# High_Side_Drivers.net
KiCad netlist of a schematic drawn in Altium Designer
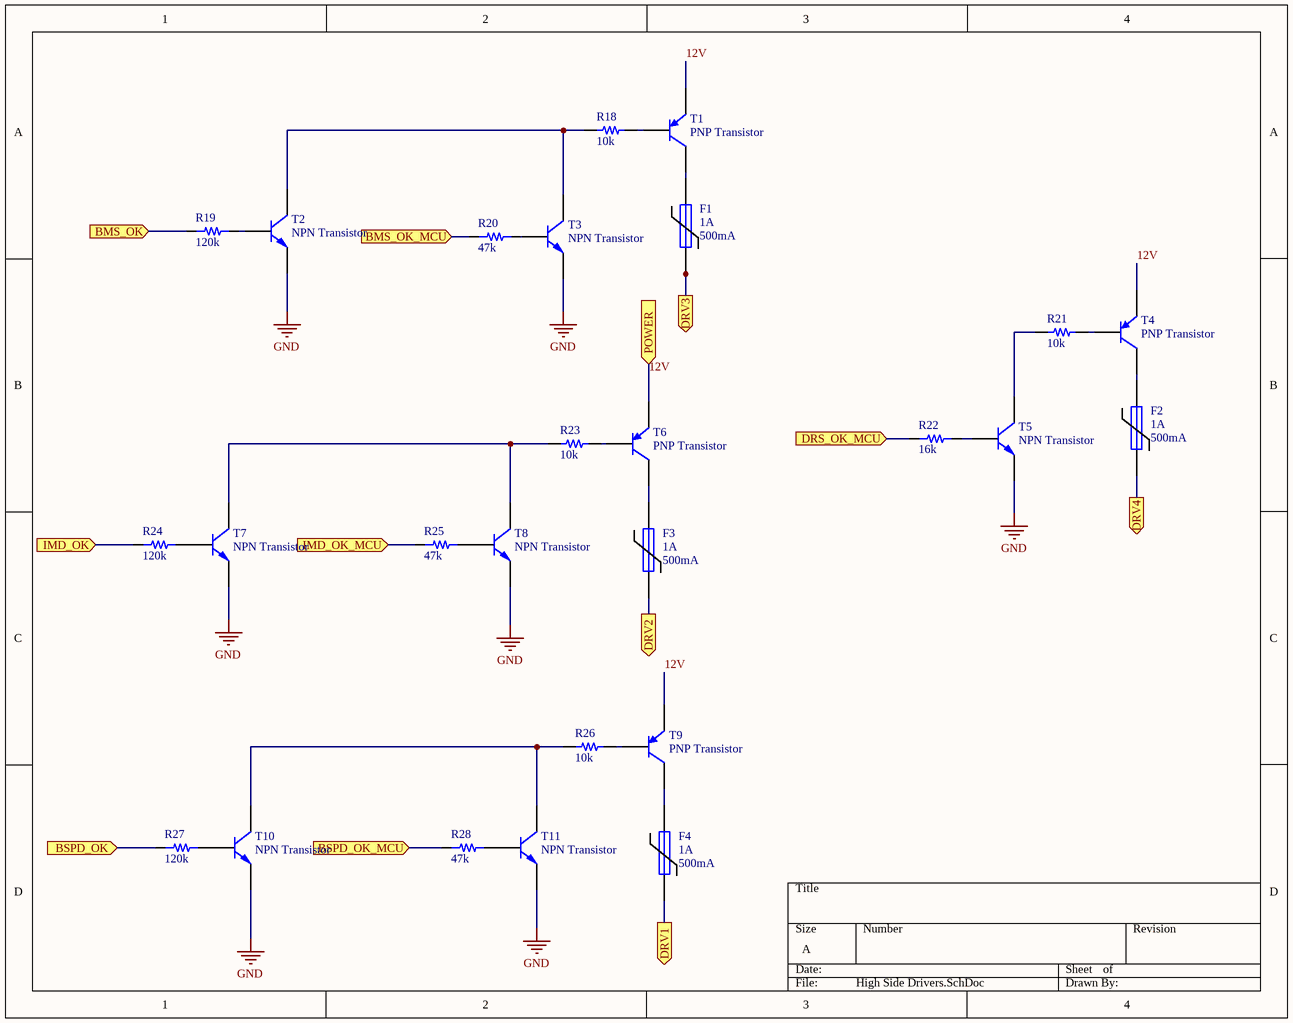
[diagram p0: High Side Drivers.SchDoc]

(export (version "E")
  (design (tool "Eeschema 10.0.6"))
  (components
    (comp (ref "F1")
      (value "1A")
      (footprint "PTC Fuse 1206/3216")
      (description "Fuse")
      (fields
        (field (name "I_HOLD") "500mA")
        (field (name "MFRPARTNO") "1206L050/15YR")
        (field (name "PUBLISHER") "Altium Limited")
        (field (name "CREATED_BY") "Angel")
      )
      (libsource (lib "Altium-Lib") (part "PTC Fuse"))
    )
    (comp (ref "F2")
      (value "1A")
      (footprint "PTC Fuse 1206/3216")
      (description "Fuse")
      (fields
        (field (name "I_HOLD") "500mA")
        (field (name "MFRPARTNO") "1206L050/15YR")
        (field (name "PUBLISHER") "Altium Limited")
        (field (name "CREATED_BY") "Angel")
      )
      (libsource (lib "Altium-Lib") (part "PTC Fuse"))
    )
    (comp (ref "F3")
      (value "1A")
      (footprint "PTC Fuse 1206/3216")
      (description "Fuse")
      (fields
        (field (name "I_HOLD") "500mA")
        (field (name "MFRPARTNO") "1206L050/15YR")
        (field (name "PUBLISHER") "Altium Limited")
        (field (name "CREATED_BY") "Angel")
      )
      (libsource (lib "Altium-Lib") (part "PTC Fuse"))
    )
    (comp (ref "F4")
      (value "1A")
      (footprint "PTC Fuse 1206/3216")
      (description "Fuse")
      (fields
        (field (name "I_HOLD") "500mA")
        (field (name "MFRPARTNO") "1206L050/15YR")
        (field (name "PUBLISHER") "Altium Limited")
        (field (name "CREATED_BY") "Angel")
      )
      (libsource (lib "Altium-Lib") (part "PTC Fuse"))
    )
    (comp (ref "R18")
      (value "10k")
      (footprint "RES 0805/2012")
      (fields
        (field (name "TOLERANCE") "5%")
        (field (name "POWER") "1/4W")
        (field (name "Comment") "Resistor 10k 0805 1/4W 5%")
        (field (name "CREATED_BY") "Nick Mah")
      )
      (libsource (lib "") (part "Resistor_1"))
    )
    (comp (ref "R19")
      (value "120k")
      (footprint "RES 0805/2012")
      (fields
        (field (name "TOLERANCE") "1%")
        (field (name "POWER") "1/4W")
        (field (name "Comment") "Resistor 120k 0805 1/4W 1%")
        (field (name "CREATED_BY") "Nick Mah")
      )
      (libsource (lib "Altium-Lib") (part "Resistor"))
    )
    (comp (ref "R20")
      (value "47k")
      (footprint "RES 0805/2012")
      (fields
        (field (name "TOLERANCE") "1%")
        (field (name "POWER") "1/4W")
        (field (name "Comment") "Resistor 47k 0805 1/4W 1%")
        (field (name "CREATED_BY") "Nick Mah")
      )
      (libsource (lib "Altium-Lib") (part "Resistor"))
    )
    (comp (ref "R21")
      (value "10k")
      (footprint "RES 0805/2012")
      (fields
        (field (name "TOLERANCE") "5%")
        (field (name "POWER") "1/4W")
        (field (name "Comment") "Resistor 10k 0805 1/4W 5%")
        (field (name "CREATED_BY") "Nick Mah")
      )
      (libsource (lib "") (part "Resistor_1"))
    )
    (comp (ref "R22")
      (value "16k")
      (footprint "RES 0805/2012")
      (fields
        (field (name "TOLERANCE") "1%")
        (field (name "POWER") "1/4W")
        (field (name "Comment") "Resistor 16k 0805 1/4W 1%")
        (field (name "CREATED_BY") "Nick Mah")
      )
      (libsource (lib "Altium-Lib") (part "Resistor"))
    )
    (comp (ref "R23")
      (value "10k")
      (footprint "RES 0805/2012")
      (fields
        (field (name "TOLERANCE") "5%")
        (field (name "POWER") "1/4W")
        (field (name "Comment") "Resistor 10k 0805 1/4W 5%")
        (field (name "CREATED_BY") "Nick Mah")
      )
      (libsource (lib "") (part "Resistor_1"))
    )
    (comp (ref "R24")
      (value "120k")
      (footprint "RES 0805/2012")
      (fields
        (field (name "TOLERANCE") "1%")
        (field (name "POWER") "1/4W")
        (field (name "Comment") "Resistor 120k 0805 1/4W 1%")
        (field (name "CREATED_BY") "Nick Mah")
      )
      (libsource (lib "Altium-Lib") (part "Resistor"))
    )
    (comp (ref "R25")
      (value "47k")
      (footprint "RES 0805/2012")
      (fields
        (field (name "TOLERANCE") "1%")
        (field (name "POWER") "1/4W")
        (field (name "Comment") "Resistor 47k 0805 1/4W 1%")
        (field (name "CREATED_BY") "Nick Mah")
      )
      (libsource (lib "Altium-Lib") (part "Resistor"))
    )
    (comp (ref "R26")
      (value "10k")
      (footprint "RES 0805/2012")
      (fields
        (field (name "TOLERANCE") "5%")
        (field (name "POWER") "1/4W")
        (field (name "Comment") "Resistor 10k 0805 1/4W 5%")
        (field (name "CREATED_BY") "Nick Mah")
      )
      (libsource (lib "") (part "Resistor_1"))
    )
    (comp (ref "R27")
      (value "120k")
      (footprint "RES 0805/2012")
      (fields
        (field (name "TOLERANCE") "1%")
        (field (name "POWER") "1/4W")
        (field (name "Comment") "Resistor 120k 0805 1/4W 1%")
        (field (name "CREATED_BY") "Nick Mah")
      )
      (libsource (lib "Altium-Lib") (part "Resistor"))
    )
    (comp (ref "R28")
      (value "47k")
      (footprint "RES 0805/2012")
      (fields
        (field (name "TOLERANCE") "1%")
        (field (name "POWER") "1/4W")
        (field (name "Comment") "Resistor 47k 0805 1/4W 1%")
        (field (name "CREATED_BY") "Nick Mah")
      )
      (libsource (lib "Altium-Lib") (part "Resistor"))
    )
    (comp (ref "T1")
      (value "PNP Transistor")
      (footprint "SOT23-3")
      (fields (field (name "MFRPARTNO") "MMBT4403WT1G") (field (name "CREATED_BY") "Angel"))
      (libsource (lib "Altium-Lib") (part "PNP Transistor"))
    )
    (comp (ref "T2")
      (value "NPN Transistor")
      (footprint "SOT23-3")
      (libsource (lib "Altium-Lib") (part "NPN Transistor"))
    )
    (comp (ref "T3")
      (value "NPN Transistor")
      (footprint "SOT23-3")
      (libsource (lib "Altium-Lib") (part "NPN Transistor"))
    )
    (comp (ref "T4")
      (value "PNP Transistor")
      (footprint "SOT23-3")
      (fields (field (name "MFRPARTNO") "MMBT4403WT1G") (field (name "CREATED_BY") "Angel"))
      (libsource (lib "Altium-Lib") (part "PNP Transistor"))
    )
    (comp (ref "T5")
      (value "NPN Transistor")
      (footprint "SOT23-3")
      (libsource (lib "Altium-Lib") (part "NPN Transistor"))
    )
    (comp (ref "T6")
      (value "PNP Transistor")
      (footprint "SOT23-3")
      (fields (field (name "MFRPARTNO") "MMBT4403WT1G") (field (name "CREATED_BY") "Angel"))
      (libsource (lib "Altium-Lib") (part "PNP Transistor"))
    )
    (comp (ref "T7")
      (value "NPN Transistor")
      (footprint "SOT23-3")
      (libsource (lib "Altium-Lib") (part "NPN Transistor"))
    )
    (comp (ref "T8")
      (value "NPN Transistor")
      (footprint "SOT23-3")
      (libsource (lib "Altium-Lib") (part "NPN Transistor"))
    )
    (comp (ref "T9")
      (value "PNP Transistor")
      (footprint "SOT23-3")
      (fields (field (name "MFRPARTNO") "MMBT4403WT1G") (field (name "CREATED_BY") "Angel"))
      (libsource (lib "Altium-Lib") (part "PNP Transistor"))
    )
    (comp (ref "T10")
      (value "NPN Transistor")
      (footprint "SOT23-3")
      (libsource (lib "Altium-Lib") (part "NPN Transistor"))
    )
    (comp (ref "T11")
      (value "NPN Transistor")
      (footprint "SOT23-3")
      (libsource (lib "Altium-Lib") (part "NPN Transistor"))
    )
  )
  (nets
    (net (code "1") (name "/12V") (class "Default")
      (node (ref "T1") (pin "2") (pinfunction "E_2") (pintype "passive"))
      (node (ref "T4") (pin "2") (pinfunction "E_2") (pintype "passive"))
      (node (ref "T6") (pin "2") (pinfunction "E_2") (pintype "passive"))
      (node (ref "T9") (pin "2") (pinfunction "E_2") (pintype "passive"))
    )
    (net (code "2") (name "/BMS_OK") (class "Default")
      (node (ref "R19") (pin "1") (pinfunction "1_1") (pintype "passive"))
    )
    (net (code "3") (name "/BMS_OK_MCU") (class "Default")
      (node (ref "R20") (pin "1") (pinfunction "1_1") (pintype "passive"))
    )
    (net (code "4") (name "/BSPD_OK") (class "Default")
      (node (ref "R27") (pin "1") (pinfunction "1_1") (pintype "passive"))
    )
    (net (code "5") (name "/BSPD_OK_MCU") (class "Default")
      (node (ref "R28") (pin "1") (pinfunction "1_1") (pintype "passive"))
    )
    (net (code "6") (name "/DRS_OK_MCU") (class "Default")
      (node (ref "R22") (pin "1") (pinfunction "1_1") (pintype "passive"))
    )
    (net (code "7") (name "/DRV1") (class "Default")
      (node (ref "F4") (pin "1") (pinfunction "1_1") (pintype "passive"))
    )
    (net (code "8") (name "/DRV2") (class "Default")
      (node (ref "F3") (pin "1") (pinfunction "1_1") (pintype "passive"))
    )
    (net (code "9") (name "/DRV3") (class "Default")
      (node (ref "F1") (pin "1") (pinfunction "1_1") (pintype "passive"))
    )
    (net (code "10") (name "/DRV4") (class "Default")
      (node (ref "F2") (pin "1") (pinfunction "1_1") (pintype "passive"))
    )
    (net (code "11") (name "/IMD_OK") (class "Default")
      (node (ref "R24") (pin "1") (pinfunction "1_1") (pintype "passive"))
    )
    (net (code "12") (name "/IMD_OK_MCU") (class "Default")
      (node (ref "R25") (pin "1") (pinfunction "1_1") (pintype "passive"))
    )
    (net (code "13") (name "GND") (class "Default")
      (node (ref "T10") (pin "1") (pinfunction "E_1") (pintype "passive"))
      (node (ref "T11") (pin "1") (pinfunction "E_1") (pintype "passive"))
      (node (ref "T2") (pin "1") (pinfunction "E_1") (pintype "passive"))
      (node (ref "T3") (pin "1") (pinfunction "E_1") (pintype "passive"))
      (node (ref "T5") (pin "1") (pinfunction "E_1") (pintype "passive"))
      (node (ref "T7") (pin "1") (pinfunction "E_1") (pintype "passive"))
      (node (ref "T8") (pin "1") (pinfunction "E_1") (pintype "passive"))
    )
    (net (code "14") (name "Net-(T1-B)") (class "Default")
      (node (ref "R18") (pin "2") (pinfunction "2_2") (pintype "passive"))
      (node (ref "T1") (pin "1") (pinfunction "B_1") (pintype "passive"))
    )
    (net (code "15") (name "Net-(T1-C)") (class "Default")
      (node (ref "F1") (pin "2") (pinfunction "2_2") (pintype "passive"))
      (node (ref "T1") (pin "3") (pinfunction "C_3") (pintype "passive"))
    )
    (net (code "16") (name "Net-(T2-B)") (class "Default")
      (node (ref "R19") (pin "2") (pinfunction "2_2") (pintype "passive"))
      (node (ref "T2") (pin "2") (pinfunction "B_2") (pintype "passive"))
    )
    (net (code "17") (name "Net-(T2-C)") (class "Default")
      (node (ref "R18") (pin "1") (pinfunction "1_1") (pintype "passive"))
      (node (ref "T2") (pin "3") (pinfunction "C_3") (pintype "passive"))
      (node (ref "T3") (pin "3") (pinfunction "C_3") (pintype "passive"))
    )
    (net (code "18") (name "Net-(T3-B)") (class "Default")
      (node (ref "R20") (pin "2") (pinfunction "2_2") (pintype "passive"))
      (node (ref "T3") (pin "2") (pinfunction "B_2") (pintype "passive"))
    )
    (net (code "19") (name "Net-(T4-B)") (class "Default")
      (node (ref "R21") (pin "2") (pinfunction "2_2") (pintype "passive"))
      (node (ref "T4") (pin "1") (pinfunction "B_1") (pintype "passive"))
    )
    (net (code "20") (name "Net-(T4-C)") (class "Default")
      (node (ref "F2") (pin "2") (pinfunction "2_2") (pintype "passive"))
      (node (ref "T4") (pin "3") (pinfunction "C_3") (pintype "passive"))
    )
    (net (code "21") (name "Net-(T5-B)") (class "Default")
      (node (ref "R22") (pin "2") (pinfunction "2_2") (pintype "passive"))
      (node (ref "T5") (pin "2") (pinfunction "B_2") (pintype "passive"))
    )
    (net (code "22") (name "Net-(T5-C)") (class "Default")
      (node (ref "R21") (pin "1") (pinfunction "1_1") (pintype "passive"))
      (node (ref "T5") (pin "3") (pinfunction "C_3") (pintype "passive"))
    )
    (net (code "23") (name "Net-(T6-B)") (class "Default")
      (node (ref "R23") (pin "2") (pinfunction "2_2") (pintype "passive"))
      (node (ref "T6") (pin "1") (pinfunction "B_1") (pintype "passive"))
    )
    (net (code "24") (name "Net-(T6-C)") (class "Default")
      (node (ref "F3") (pin "2") (pinfunction "2_2") (pintype "passive"))
      (node (ref "T6") (pin "3") (pinfunction "C_3") (pintype "passive"))
    )
    (net (code "25") (name "Net-(T7-B)") (class "Default")
      (node (ref "R24") (pin "2") (pinfunction "2_2") (pintype "passive"))
      (node (ref "T7") (pin "2") (pinfunction "B_2") (pintype "passive"))
    )
    (net (code "26") (name "Net-(T7-C)") (class "Default")
      (node (ref "R23") (pin "1") (pinfunction "1_1") (pintype "passive"))
      (node (ref "T7") (pin "3") (pinfunction "C_3") (pintype "passive"))
      (node (ref "T8") (pin "3") (pinfunction "C_3") (pintype "passive"))
    )
    (net (code "27") (name "Net-(T8-B)") (class "Default")
      (node (ref "R25") (pin "2") (pinfunction "2_2") (pintype "passive"))
      (node (ref "T8") (pin "2") (pinfunction "B_2") (pintype "passive"))
    )
    (net (code "28") (name "Net-(T9-B)") (class "Default")
      (node (ref "R26") (pin "2") (pinfunction "2_2") (pintype "passive"))
      (node (ref "T9") (pin "1") (pinfunction "B_1") (pintype "passive"))
    )
    (net (code "29") (name "Net-(T9-C)") (class "Default")
      (node (ref "F4") (pin "2") (pinfunction "2_2") (pintype "passive"))
      (node (ref "T9") (pin "3") (pinfunction "C_3") (pintype "passive"))
    )
    (net (code "30") (name "Net-(T10-B)") (class "Default")
      (node (ref "R27") (pin "2") (pinfunction "2_2") (pintype "passive"))
      (node (ref "T10") (pin "2") (pinfunction "B_2") (pintype "passive"))
    )
    (net (code "31") (name "Net-(T10-C)") (class "Default")
      (node (ref "R26") (pin "1") (pinfunction "1_1") (pintype "passive"))
      (node (ref "T10") (pin "3") (pinfunction "C_3") (pintype "passive"))
      (node (ref "T11") (pin "3") (pinfunction "C_3") (pintype "passive"))
    )
    (net (code "32") (name "Net-(T11-B)") (class "Default")
      (node (ref "R28") (pin "2") (pinfunction "2_2") (pintype "passive"))
      (node (ref "T11") (pin "2") (pinfunction "B_2") (pintype "passive"))
    )
  )
)
